# 467999_001_3_2.net
KiCad netlist of a schematic drawn in Altium Designer
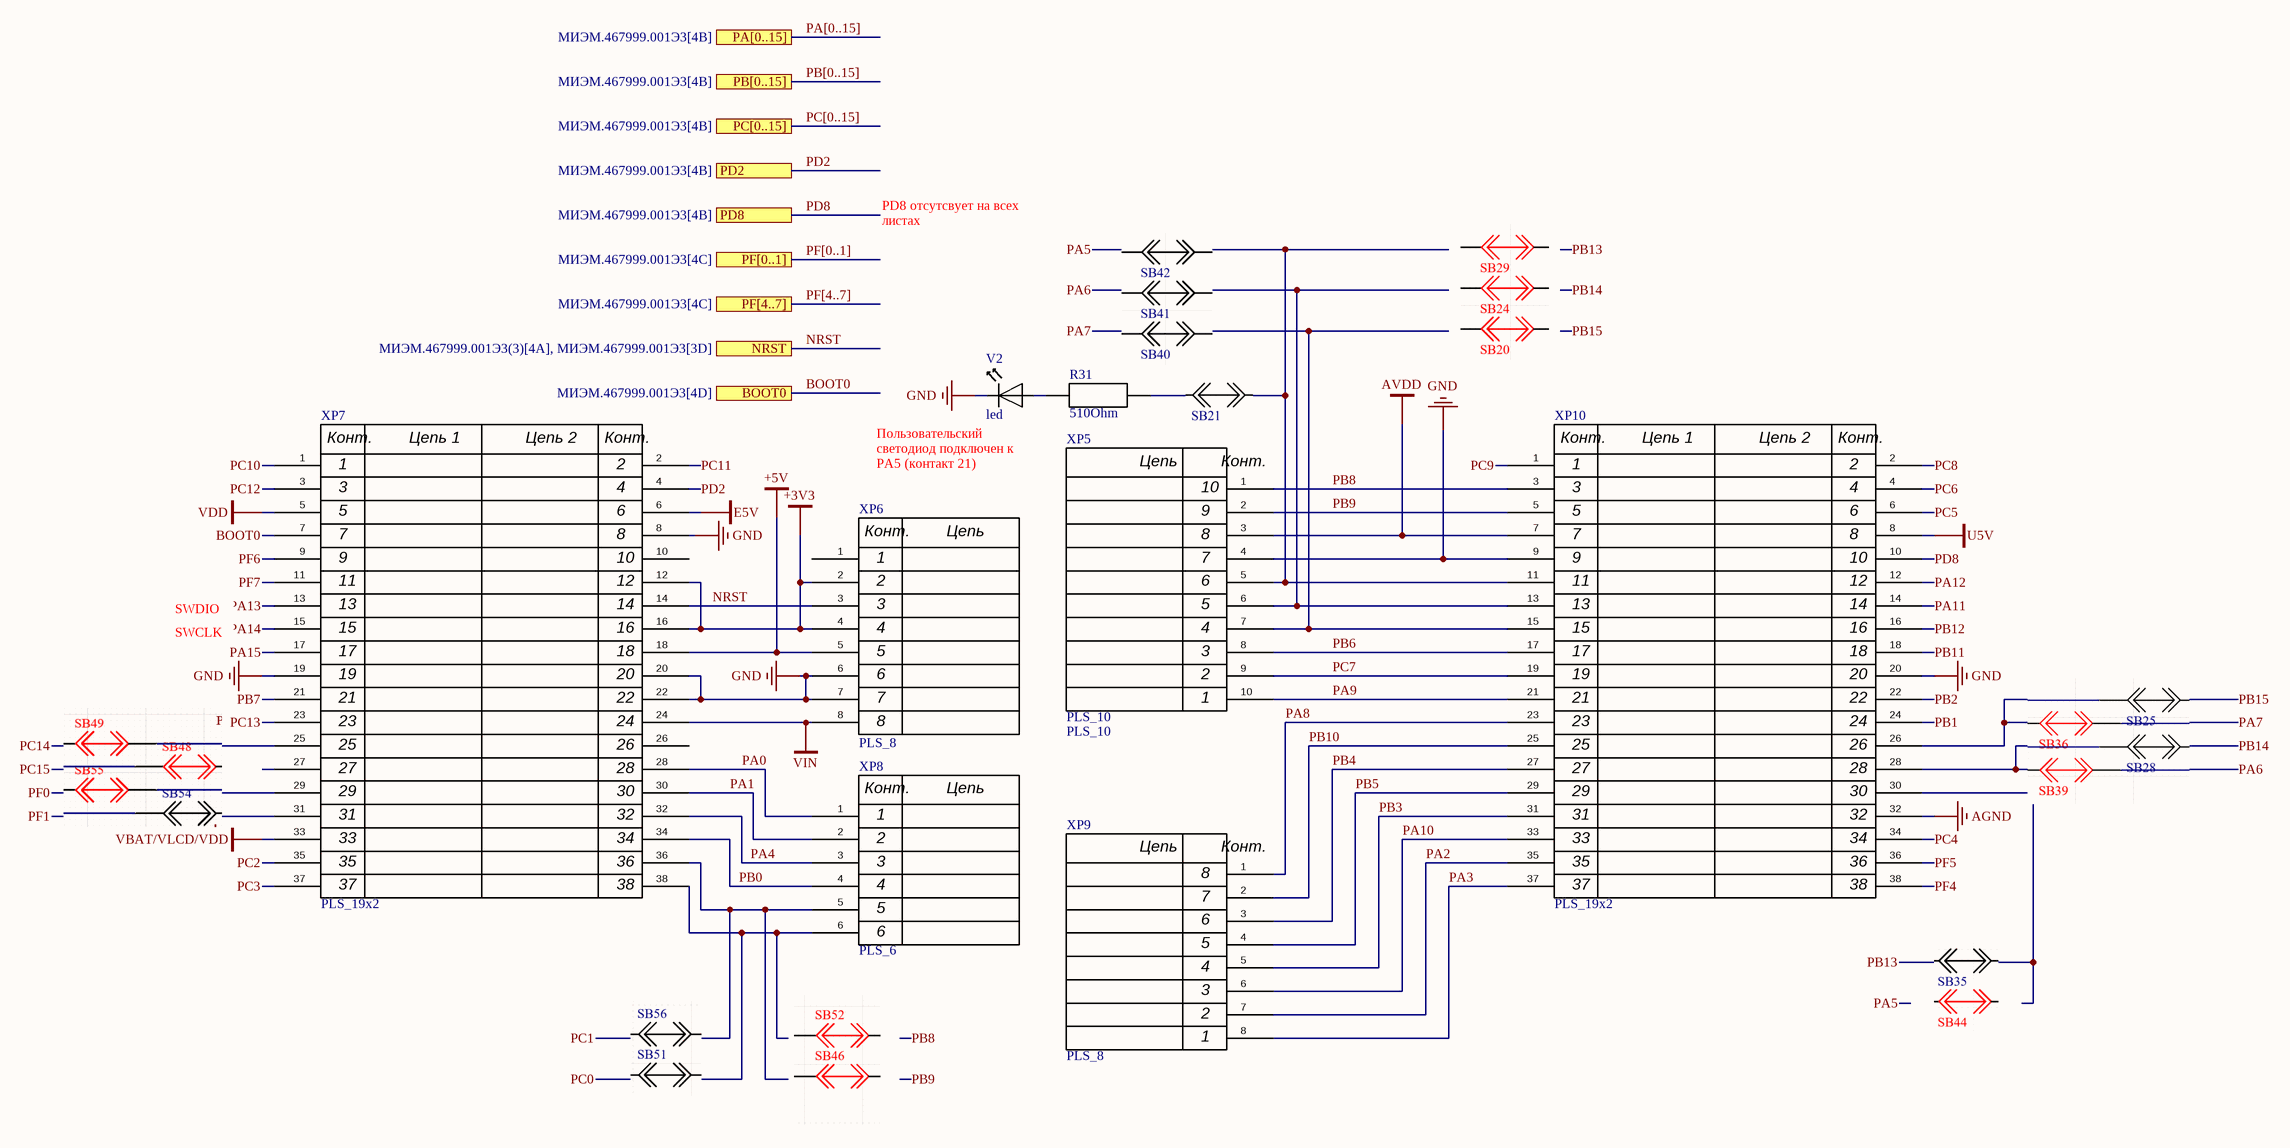
[diagram p0: МИЭМ.467999.001Э3(2).SchDoc]

(export (version "E")
  (design (tool "Eeschema 10.0.6"))
  (components
    (comp (ref "R31")
      (value "510Ohm")
      (footprint "0603")
      (fields
        (field (name "POWER") "0.063Вт")
        (field (name "TOLERANCE") "1%")
        (field (name "PARTNUMBER") "RC0603FR-07510RL")
      )
      (libsource (lib "Resistor_GOST") (part "Resistor"))
    )
    (comp (ref "V2")
      (value "led")
      (footprint "FYLS-0603PGC")
      (fields
        (field (name "PARTNUMBER") "FYLS-0603PGC")
        (field (name "MANUFACTURER") "Ningbo Foryard Optoelectronics")
      )
      (libsource (lib "diodes_semiconductors_GOST") (part "led"))
    )
    (comp (ref "XP5")
      (value "PLS_10")
      (footprint "PLS_10")
      (fields (field (name "PARTNUMBER") "PLS_10"))
      (libsource (lib "Connector_GOST") (part "PLS_10"))
    )
    (comp (ref "XP6") (value "PLS_8") (footprint "PLS_8") (libsource (lib "Connector_GOST") (part "PLS_8")))
    (comp (ref "XP7")
      (value "PLS_19x2")
      (footprint "PLS_19x2")
      (libsource (lib "Connector_GOST") (part "PLS_19x2"))
    )
    (comp (ref "XP8") (value "PLS_6") (footprint "PLS_6") (libsource (lib "Connector_GOST") (part "PLS_6")))
    (comp (ref "XP9") (value "PLS_8") (footprint "PLS_8") (libsource (lib "") (part "PLS_8_1")))
    (comp (ref "XP10")
      (value "PLS_19x2")
      (footprint "PLS_19x2")
      (libsource (lib "Connector_GOST") (part "PLS_19x2"))
    )
  )
  (nets
    (net (code "1") (name "+3V3") (class "Default")
      (node (ref "XP6") (pin "2") (pinfunction "2_2") (pintype "passive"))
      (node (ref "XP6") (pin "4") (pinfunction "4_4") (pintype "passive"))
      (node (ref "XP7") (pin "12") (pinfunction "12_12") (pintype "passive"))
      (node (ref "XP7") (pin "16") (pinfunction "16_16") (pintype "passive"))
    )
    (net (code "2") (name "+5V") (class "Default")
      (node (ref "XP6") (pin "5") (pinfunction "5_5") (pintype "passive"))
      (node (ref "XP7") (pin "18") (pinfunction "18_18") (pintype "passive"))
    )
    (net (code "3") (name "/BOOT0") (class "Default")
      (node (ref "XP7") (pin "7") (pinfunction "7_7") (pintype "passive"))
    )
    (net (code "4") (name "/NRST") (class "Default")
      (node (ref "XP6") (pin "3") (pinfunction "3_3") (pintype "passive"))
      (node (ref "XP7") (pin "14") (pinfunction "14_14") (pintype "passive"))
    )
    (net (code "5") (name "/PA0") (class "Default")
      (node (ref "XP7") (pin "28") (pinfunction "28_28") (pintype "passive"))
      (node (ref "XP8") (pin "1") (pinfunction "1_1") (pintype "passive"))
    )
    (net (code "6") (name "/PA1") (class "Default")
      (node (ref "XP7") (pin "30") (pinfunction "30_30") (pintype "passive"))
      (node (ref "XP8") (pin "2") (pinfunction "2_2") (pintype "passive"))
    )
    (net (code "7") (name "/PA2") (class "Default")
      (node (ref "XP10") (pin "35") (pinfunction "35_35") (pintype "passive"))
      (node (ref "XP9") (pin "7") (pinfunction "7_7") (pintype "passive"))
    )
    (net (code "8") (name "/PA3") (class "Default")
      (node (ref "XP10") (pin "37") (pinfunction "37_37") (pintype "passive"))
      (node (ref "XP9") (pin "8") (pinfunction "8_8") (pintype "passive"))
    )
    (net (code "9") (name "/PA4") (class "Default")
      (node (ref "XP7") (pin "32") (pinfunction "32_32") (pintype "passive"))
      (node (ref "XP8") (pin "3") (pinfunction "3_3") (pintype "passive"))
    )
    (net (code "10") (name "/PA5") (class "Default")
      (node (ref "R31") (pin "2") (pinfunction "2_2") (pintype "passive"))
      (node (ref "XP10") (pin "11") (pinfunction "11_11") (pintype "passive"))
      (node (ref "XP5") (pin "5") (pinfunction "5_5") (pintype "passive"))
    )
    (net (code "11") (name "/PA6") (class "Default")
      (node (ref "XP10") (pin "13") (pinfunction "13_13") (pintype "passive"))
      (node (ref "XP5") (pin "6") (pinfunction "6_6") (pintype "passive"))
    )
    (net (code "12") (name "/PA7") (class "Default")
      (node (ref "XP10") (pin "15") (pinfunction "15_15") (pintype "passive"))
      (node (ref "XP5") (pin "7") (pinfunction "7_7") (pintype "passive"))
    )
    (net (code "13") (name "/PA8") (class "Default")
      (node (ref "XP10") (pin "23") (pinfunction "23_23") (pintype "passive"))
      (node (ref "XP9") (pin "1") (pinfunction "1_1") (pintype "passive"))
    )
    (net (code "14") (name "/PA9") (class "Default")
      (node (ref "XP10") (pin "21") (pinfunction "21_21") (pintype "passive"))
      (node (ref "XP5") (pin "10") (pinfunction "10_10") (pintype "passive"))
    )
    (net (code "15") (name "/PA10") (class "Default")
      (node (ref "XP10") (pin "33") (pinfunction "33_33") (pintype "passive"))
      (node (ref "XP9") (pin "6") (pinfunction "6_6") (pintype "passive"))
    )
    (net (code "16") (name "/PA11") (class "Default")
      (node (ref "XP10") (pin "14") (pinfunction "14_14") (pintype "passive"))
    )
    (net (code "17") (name "/PA12") (class "Default")
      (node (ref "XP10") (pin "12") (pinfunction "12_12") (pintype "passive"))
    )
    (net (code "18") (name "/PA13") (class "Default")
      (node (ref "XP7") (pin "13") (pinfunction "13_13") (pintype "passive"))
    )
    (net (code "19") (name "/PA14") (class "Default")
      (node (ref "XP7") (pin "15") (pinfunction "15_15") (pintype "passive"))
    )
    (net (code "20") (name "/PA15") (class "Default")
      (node (ref "XP7") (pin "17") (pinfunction "17_17") (pintype "passive"))
    )
    (net (code "22") (name "/PB0") (class "Default")
      (node (ref "XP7") (pin "34") (pinfunction "34_34") (pintype "passive"))
      (node (ref "XP8") (pin "4") (pinfunction "4_4") (pintype "passive"))
    )
    (net (code "23") (name "/PB1") (class "Default")
      (node (ref "XP10") (pin "24") (pinfunction "24_24") (pintype "passive"))
    )
    (net (code "24") (name "/PB2") (class "Default")
      (node (ref "XP10") (pin "22") (pinfunction "22_22") (pintype "passive"))
    )
    (net (code "25") (name "/PB3") (class "Default")
      (node (ref "XP10") (pin "31") (pinfunction "31_31") (pintype "passive"))
      (node (ref "XP9") (pin "5") (pinfunction "5_5") (pintype "passive"))
    )
    (net (code "26") (name "/PB4") (class "Default")
      (node (ref "XP10") (pin "27") (pinfunction "27_27") (pintype "passive"))
      (node (ref "XP9") (pin "3") (pinfunction "3_3") (pintype "passive"))
    )
    (net (code "27") (name "/PB5") (class "Default")
      (node (ref "XP10") (pin "29") (pinfunction "29_29") (pintype "passive"))
      (node (ref "XP9") (pin "4") (pinfunction "4_4") (pintype "passive"))
    )
    (net (code "28") (name "/PB6") (class "Default")
      (node (ref "XP10") (pin "17") (pinfunction "17_17") (pintype "passive"))
      (node (ref "XP5") (pin "8") (pinfunction "8_8") (pintype "passive"))
    )
    (net (code "29") (name "/PB7") (class "Default")
      (node (ref "XP7") (pin "21") (pinfunction "21_21") (pintype "passive"))
    )
    (net (code "30") (name "/PB8") (class "Default")
      (node (ref "XP10") (pin "3") (pinfunction "3_3") (pintype "passive"))
      (node (ref "XP5") (pin "1") (pinfunction "1_1") (pintype "passive"))
    )
    (net (code "31") (name "/PB9") (class "Default")
      (node (ref "XP10") (pin "5") (pinfunction "5_5") (pintype "passive"))
      (node (ref "XP5") (pin "2") (pinfunction "2_2") (pintype "passive"))
    )
    (net (code "32") (name "/PB10") (class "Default")
      (node (ref "XP10") (pin "25") (pinfunction "25_25") (pintype "passive"))
      (node (ref "XP9") (pin "2") (pinfunction "2_2") (pintype "passive"))
    )
    (net (code "33") (name "/PB11") (class "Default")
      (node (ref "XP10") (pin "18") (pinfunction "18_18") (pintype "passive"))
    )
    (net (code "34") (name "/PB12") (class "Default")
      (node (ref "XP10") (pin "16") (pinfunction "16_16") (pintype "passive"))
    )
    (net (code "35") (name "/PB13") (class "Default")
      (node (ref "XP10") (pin "30") (pinfunction "30_30") (pintype "passive"))
    )
    (net (code "36") (name "/PB14") (class "Default")
      (node (ref "XP10") (pin "28") (pinfunction "28_28") (pintype "passive"))
    )
    (net (code "37") (name "/PB15") (class "Default")
      (node (ref "XP10") (pin "26") (pinfunction "26_26") (pintype "passive"))
    )
    (net (code "39") (name "/PC0") (class "Default")
      (node (ref "XP7") (pin "38") (pinfunction "38_38") (pintype "passive"))
      (node (ref "XP8") (pin "6") (pinfunction "6_6") (pintype "passive"))
    )
    (net (code "40") (name "/PC1") (class "Default")
      (node (ref "XP7") (pin "36") (pinfunction "36_36") (pintype "passive"))
      (node (ref "XP8") (pin "5") (pinfunction "5_5") (pintype "passive"))
    )
    (net (code "41") (name "/PC2") (class "Default")
      (node (ref "XP7") (pin "35") (pinfunction "35_35") (pintype "passive"))
    )
    (net (code "42") (name "/PC3") (class "Default")
      (node (ref "XP7") (pin "37") (pinfunction "37_37") (pintype "passive"))
    )
    (net (code "43") (name "/PC4") (class "Default")
      (node (ref "XP10") (pin "34") (pinfunction "34_34") (pintype "passive"))
    )
    (net (code "44") (name "/PC5") (class "Default")
      (node (ref "XP10") (pin "6") (pinfunction "6_6") (pintype "passive"))
    )
    (net (code "45") (name "/PC6") (class "Default")
      (node (ref "XP10") (pin "4") (pinfunction "4_4") (pintype "passive"))
    )
    (net (code "46") (name "/PC7") (class "Default")
      (node (ref "XP10") (pin "19") (pinfunction "19_19") (pintype "passive"))
      (node (ref "XP5") (pin "9") (pinfunction "9_9") (pintype "passive"))
    )
    (net (code "47") (name "/PC8") (class "Default")
      (node (ref "XP10") (pin "2") (pinfunction "2_2") (pintype "passive"))
    )
    (net (code "48") (name "/PC9") (class "Default")
      (node (ref "XP10") (pin "1") (pinfunction "1_1") (pintype "passive"))
    )
    (net (code "49") (name "/PC10") (class "Default")
      (node (ref "XP7") (pin "1") (pinfunction "1_1") (pintype "passive"))
    )
    (net (code "50") (name "/PC11") (class "Default")
      (node (ref "XP7") (pin "2") (pinfunction "2_2") (pintype "passive"))
    )
    (net (code "51") (name "/PC12") (class "Default")
      (node (ref "XP7") (pin "3") (pinfunction "3_3") (pintype "passive"))
    )
    (net (code "52") (name "/PC13") (class "Default")
      (node (ref "XP7") (pin "23") (pinfunction "23_23") (pintype "passive"))
    )
    (net (code "56") (name "/PD2") (class "Default")
      (node (ref "XP7") (pin "4") (pinfunction "4_4") (pintype "passive"))
    )
    (net (code "57") (name "/PD8") (class "Default")
      (node (ref "XP10") (pin "10") (pinfunction "10_10") (pintype "passive"))
    )
    (net (code "59") (name "/PF1") (class "Default")
      (node (ref "XP7") (pin "31") (pinfunction "31_31") (pintype "passive"))
    )
    (net (code "60") (name "/PF4") (class "Default")
      (node (ref "XP10") (pin "38") (pinfunction "38_38") (pintype "passive"))
    )
    (net (code "61") (name "/PF5") (class "Default")
      (node (ref "XP10") (pin "36") (pinfunction "36_36") (pintype "passive"))
    )
    (net (code "62") (name "/PF6") (class "Default")
      (node (ref "XP7") (pin "9") (pinfunction "9_9") (pintype "passive"))
    )
    (net (code "63") (name "/PF7") (class "Default")
      (node (ref "XP7") (pin "11") (pinfunction "11_11") (pintype "passive"))
    )
    (net (code "66") (name "AGND") (class "Default")
      (node (ref "XP10") (pin "32") (pinfunction "32_32") (pintype "passive"))
    )
    (net (code "67") (name "AVDD") (class "Default")
      (node (ref "XP10") (pin "7") (pinfunction "7_7") (pintype "passive"))
      (node (ref "XP5") (pin "3") (pinfunction "3_3") (pintype "passive"))
    )
    (net (code "68") (name "E5V") (class "Default")
      (node (ref "XP7") (pin "6") (pinfunction "6_6") (pintype "passive"))
    )
    (net (code "69") (name "GND") (class "Default")
      (node (ref "V2") (pin "2") (pinfunction "2_2") (pintype "passive"))
      (node (ref "XP10") (pin "20") (pinfunction "20_20") (pintype "passive"))
      (node (ref "XP10") (pin "9") (pinfunction "9_9") (pintype "passive"))
      (node (ref "XP5") (pin "4") (pinfunction "4_4") (pintype "passive"))
      (node (ref "XP6") (pin "6") (pinfunction "6_6") (pintype "passive"))
      (node (ref "XP6") (pin "7") (pinfunction "7_7") (pintype "passive"))
      (node (ref "XP7") (pin "19") (pinfunction "19_19") (pintype "passive"))
      (node (ref "XP7") (pin "20") (pinfunction "20_20") (pintype "passive"))
      (node (ref "XP7") (pin "22") (pinfunction "22_22") (pintype "passive"))
      (node (ref "XP7") (pin "8") (pinfunction "8_8") (pintype "passive"))
    )
    (net (code "70") (name "Net-(R31-Pad1)") (class "Default")
      (node (ref "R31") (pin "1") (pinfunction "1_1") (pintype "passive"))
      (node (ref "V2") (pin "1") (pinfunction "1_1") (pintype "passive"))
    )
    (net (code "71") (name "U5V") (class "Default")
      (node (ref "XP10") (pin "8") (pinfunction "8_8") (pintype "passive"))
    )
    (net (code "72") (name "VBAT{slash}VLCD{slash}VDD") (class "Default")
      (node (ref "XP7") (pin "33") (pinfunction "33_33") (pintype "passive"))
    )
    (net (code "73") (name "VDD") (class "Default")
      (node (ref "XP7") (pin "5") (pinfunction "5_5") (pintype "passive"))
    )
    (net (code "74") (name "VIN") (class "Default")
      (node (ref "XP6") (pin "8") (pinfunction "8_8") (pintype "passive"))
      (node (ref "XP7") (pin "24") (pinfunction "24_24") (pintype "passive"))
    )
    (net (code "75") (name "unconnected-(XP6-Pad1)") (class "Default")
      (node (ref "XP6") (pin "1") (pinfunction "1_1") (pintype "passive"))
    )
    (net (code "76") (name "unconnected-(XP7-Pad10)") (class "Default")
      (node (ref "XP7") (pin "10") (pinfunction "10_10") (pintype "passive"))
    )
    (net (code "77") (name "unconnected-(XP7-Pad25)") (class "Default")
      (node (ref "XP7") (pin "25") (pinfunction "25_25") (pintype "passive"))
    )
    (net (code "78") (name "unconnected-(XP7-Pad26)") (class "Default")
      (node (ref "XP7") (pin "26") (pinfunction "26_26") (pintype "passive"))
    )
    (net (code "79") (name "unconnected-(XP7-Pad27)") (class "Default")
      (node (ref "XP7") (pin "27") (pinfunction "27_27") (pintype "passive"))
    )
    (net (code "80") (name "unconnected-(XP7-Pad29)") (class "Default")
      (node (ref "XP7") (pin "29") (pinfunction "29_29") (pintype "passive"))
    )
  )
)
